# schematic_mach_boost_6009.net
KiCad netlist of a schematic drawn in Altium Designer
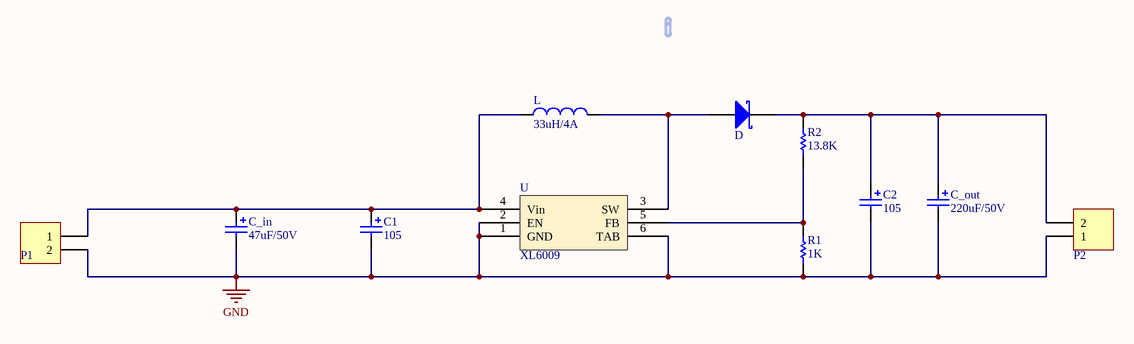
[diagram p0: schematic_mach_boost_6009.SchDoc]

(export (version "E")
  (design (tool "Eeschema 10.0.6"))
  (components
    (comp (ref "C1")
      (value "105")
      (footprint "CAP ALU SIZE B")
      (description "Polarized Capacitor (Radial)")
      (fields (field (name "Comment") "Cap Pol SMD"))
      (libsource (lib "PIF_Library") (part "Cap Pol SMD"))
    )
    (comp (ref "C2")
      (value "105")
      (footprint "CAP ALU SIZE B")
      (description "Polarized Capacitor (Radial)")
      (fields (field (name "Comment") "Cap Pol SMD"))
      (libsource (lib "PIF_Library") (part "Cap Pol SMD"))
    )
    (comp (ref "C_in")
      (value "47uF/50V")
      (footprint "CP1/2")
      (description "Polarized Capacitor (Radial)")
      (fields (field (name "Comment") "Cap Pol"))
      (libsource (lib "PIF_Library") (part "Cap Pol"))
    )
    (comp (ref "C_out")
      (value "220uF/50V")
      (footprint "CP1/2")
      (description "Polarized Capacitor (Radial)")
      (fields (field (name "Comment") "Cap Pol"))
      (libsource (lib "PIF_Library") (part "Cap Pol"))
    )
    (comp (ref "D")
      (value "D Schottky")
      (footprint "SS34")
      (description "Schottky Diode")
      (fields (field (name "PUBLISHER") "Altium Limited"))
      (libsource (lib "PIF_Library") (part "D Schottky"))
    )
    (comp (ref "L")
      (value "33uH/4A")
      (footprint "INDUCTOR 12.5x12.5")
      (description "Inductor")
      (libsource (lib "PIF_Library") (part "Inductor"))
    )
    (comp (ref "P1")
      (value "Domino 2")
      (footprint "DOMINO 2- 5mm")
      (description "Domino, 2-Pin")
      (fields (field (name "PUBLISHER") "Altium Limited"))
      (libsource (lib "PIF_Library") (part "Domino 2"))
    )
    (comp (ref "P2")
      (value "Domino 2")
      (footprint "DOMINO 2- 5mm")
      (description "Domino, 2-Pin")
      (fields (field (name "PUBLISHER") "Altium Limited"))
      (libsource (lib "") (part "Domino 2_1"))
    )
    (comp (ref "R1")
      (value "1K")
      (footprint "RES-SM-0603")
      (description "Resistor")
      (fields (field (name "Comment") "RESISTOR SMD"))
      (libsource (lib "PIF_Library") (part "RESISTOR SMD"))
    )
    (comp (ref "R2")
      (value "13.8K")
      (footprint "RES-SM-0603")
      (description "Resistor")
      (fields (field (name "Comment") "RESISTOR SMD"))
      (libsource (lib "PIF_Library") (part "RESISTOR SMD"))
    )
    (comp (ref "U")
      (value "XL6009")
      (footprint "LM2596")
      (description "SMD")
      (libsource (lib "buck&boost") (part "XL6009"))
    )
  )
  (nets
    (net (code "1") (name "GND") (class "Default")
      (node (ref "C1") (pin "2") (pinfunction "2_2") (pintype "passive"))
      (node (ref "C2") (pin "2") (pinfunction "2_2") (pintype "passive"))
      (node (ref "C_in") (pin "2") (pinfunction "2_2") (pintype "passive"))
      (node (ref "C_out") (pin "2") (pinfunction "2_2") (pintype "passive"))
      (node (ref "P1") (pin "2") (pinfunction "2_2") (pintype "passive"))
      (node (ref "P2") (pin "1") (pinfunction "1_1") (pintype "passive"))
      (node (ref "R1") (pin "1") (pinfunction "1_1") (pintype "passive"))
      (node (ref "U") (pin "1") (pinfunction "GND_1") (pintype "passive"))
      (node (ref "U") (pin "2") (pinfunction "EN_2") (pintype "passive"))
      (node (ref "U") (pin "6") (pinfunction "TAB_6") (pintype "passive"))
    )
    (net (code "2") (name "Net-(D-A)") (class "Default")
      (node (ref "D") (pin "1") (pinfunction "A_1") (pintype "passive"))
      (node (ref "L") (pin "2") (pinfunction "2_2") (pintype "passive"))
      (node (ref "U") (pin "3") (pinfunction "SW_3") (pintype "passive"))
    )
    (net (code "3") (name "Net-(D-K)") (class "Default")
      (node (ref "C2") (pin "1") (pinfunction "1_1") (pintype "passive"))
      (node (ref "C_out") (pin "1") (pinfunction "1_1") (pintype "passive"))
      (node (ref "D") (pin "2") (pinfunction "K_2") (pintype "passive"))
      (node (ref "P2") (pin "2") (pinfunction "2_2") (pintype "passive"))
      (node (ref "R2") (pin "2") (pinfunction "2_2") (pintype "passive"))
    )
    (net (code "4") (name "Net-(U-FB)") (class "Default")
      (node (ref "R1") (pin "2") (pinfunction "2_2") (pintype "passive"))
      (node (ref "R2") (pin "1") (pinfunction "1_1") (pintype "passive"))
      (node (ref "U") (pin "5") (pinfunction "FB_5") (pintype "passive"))
    )
    (net (code "5") (name "Net-(U-Vin)") (class "Default")
      (node (ref "C1") (pin "1") (pinfunction "1_1") (pintype "passive"))
      (node (ref "C_in") (pin "1") (pinfunction "1_1") (pintype "passive"))
      (node (ref "L") (pin "1") (pinfunction "1_1") (pintype "passive"))
      (node (ref "P1") (pin "1") (pinfunction "1_1") (pintype "passive"))
      (node (ref "U") (pin "4") (pinfunction "Vin_4") (pintype "passive"))
    )
  )
)
